# MCU48pin.net
KiCad netlist of a schematic drawn in Altium Designer
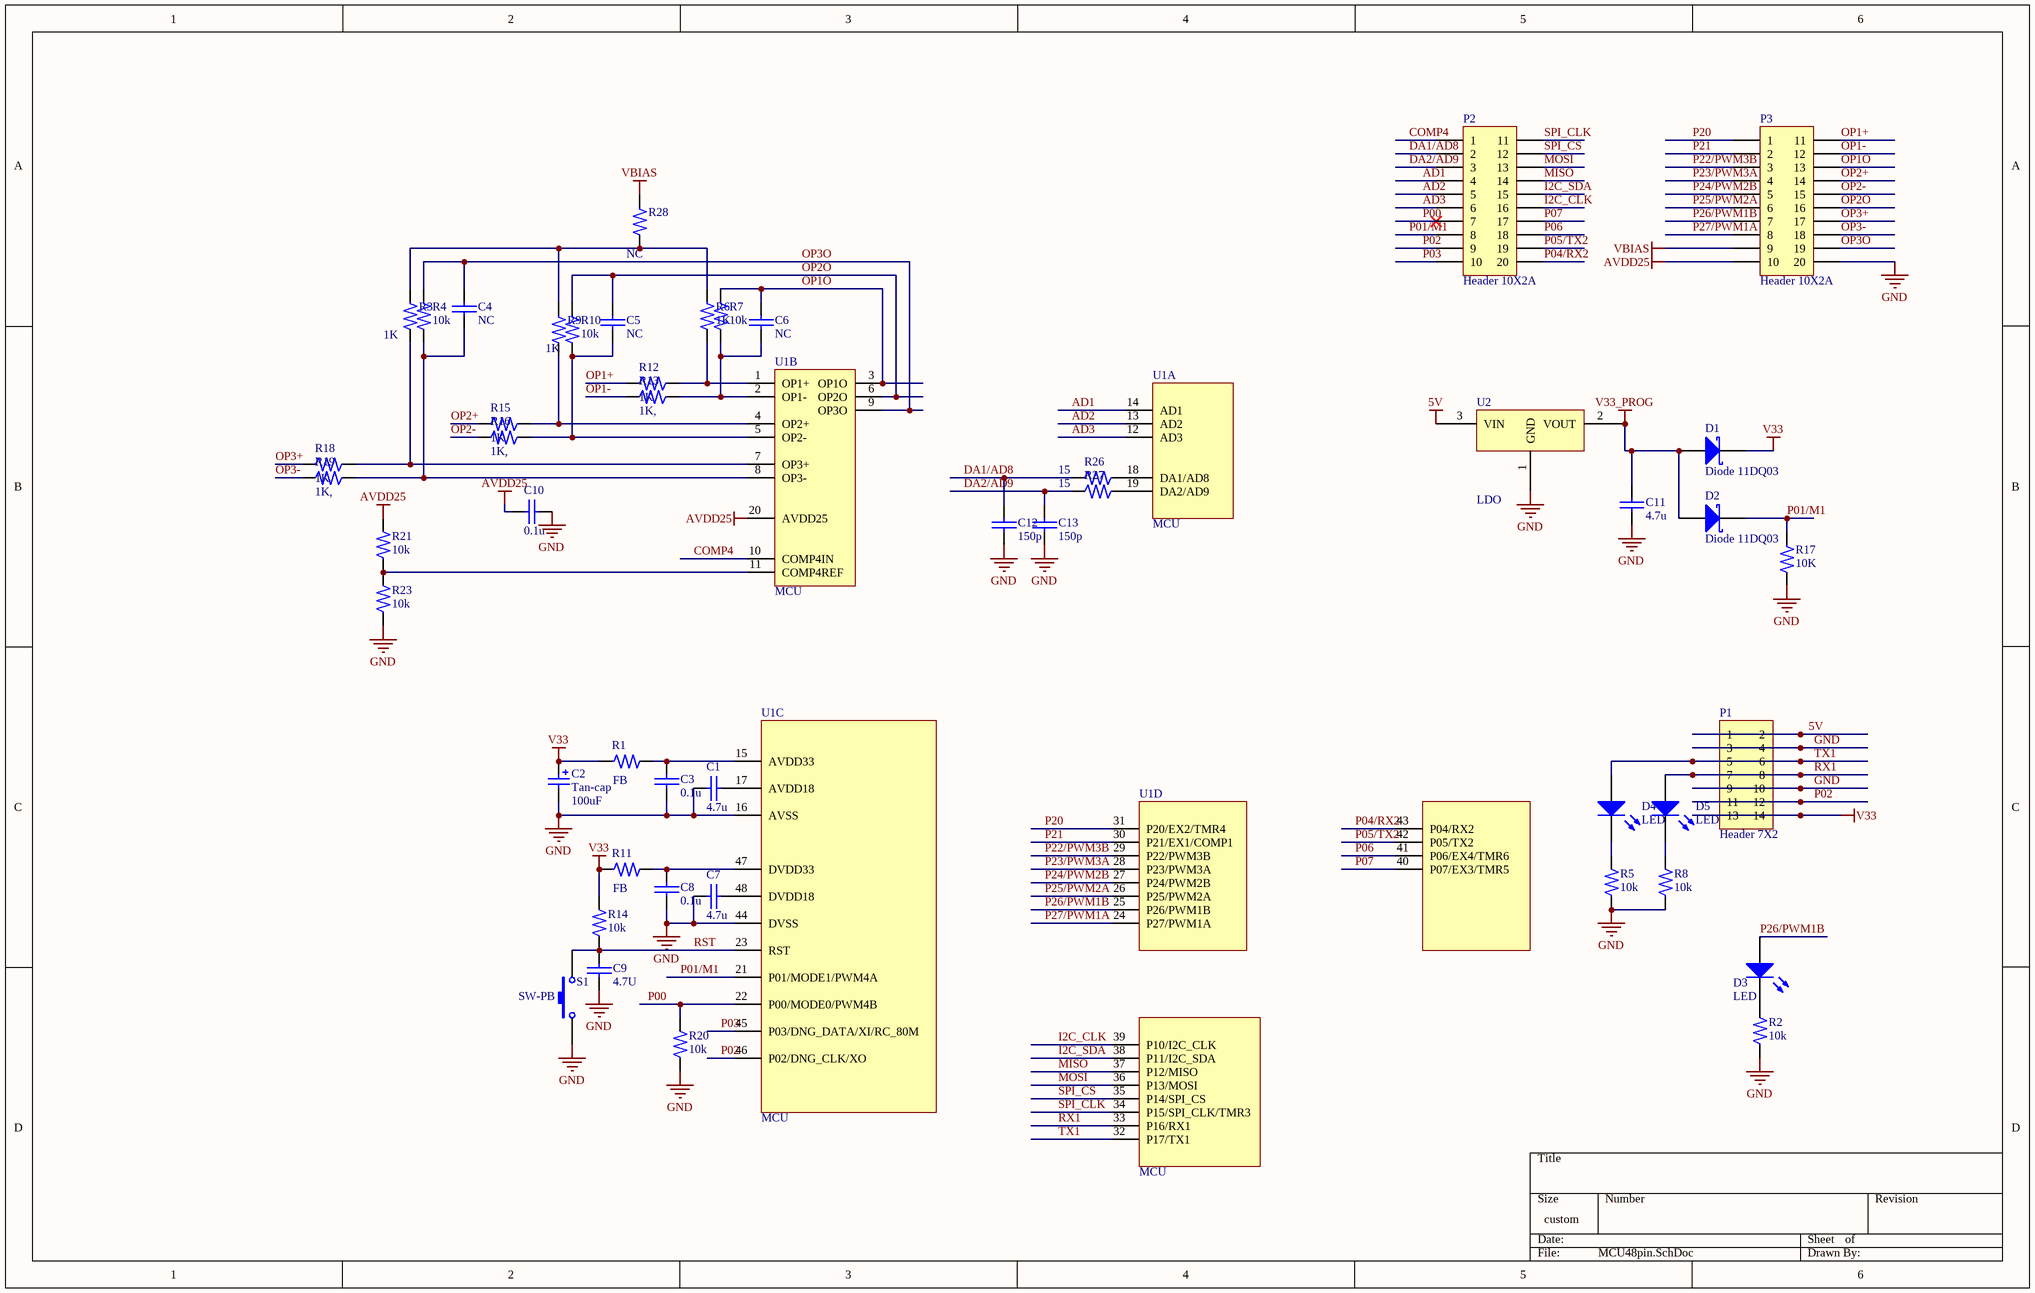
[diagram p0: MCU48pin.SchDoc]

(export (version "E")
  (design (tool "Eeschema 10.0.6"))
  (components
    (comp (ref "C1")
      (value "4.7u")
      (footprint "C0805")
      (description "CAP NL")
      (fields (field (name "MANUFACTURER") "Yageo") (field (name "PART NUMBER") "CC0603KRX7R9BB103"))
      (libsource (lib "black_V1") (part "CAP NP"))
    )
    (comp (ref "C2")
      (value "Tan-cap")
      (footprint "R1206w")
      (description "Polarized Capacitor (Radial)")
      (fields (field (name "ALTIUM_VALUE") "100uF") (field (name "PUBLISHER") "Altium Limited"))
      (libsource (lib "black_V1") (part "Cap Pol1"))
    )
    (comp (ref "C3")
      (value "0.1u")
      (footprint "1608[0603]")
      (description "CAP NL")
      (fields (field (name "MANUFACTURER") "Yageo") (field (name "PART NUMBER") "CC0603KRX7R9BB103"))
      (libsource (lib "black_V1") (part "CAP NP"))
    )
    (comp (ref "C4")
      (value "NC")
      (footprint "1608[0603]")
      (description "CAP NL")
      (fields (field (name "MANUFACTURER") "Yageo") (field (name "PART NUMBER") "CC0603KRX7R9BB103"))
      (libsource (lib "black_V1") (part "CAP NP"))
    )
    (comp (ref "C5")
      (value "NC")
      (footprint "1608[0603]")
      (description "CAP NL")
      (fields (field (name "MANUFACTURER") "Yageo") (field (name "PART NUMBER") "CC0603KRX7R9BB103"))
      (libsource (lib "black_V1") (part "CAP NP"))
    )
    (comp (ref "C6")
      (value "NC")
      (footprint "1608[0603]")
      (description "CAP NL")
      (fields (field (name "MANUFACTURER") "Yageo") (field (name "PART NUMBER") "CC0603KRX7R9BB103"))
      (libsource (lib "black_V1") (part "CAP NP"))
    )
    (comp (ref "C7")
      (value "4.7u")
      (footprint "C0805")
      (description "CAP NL")
      (fields (field (name "MANUFACTURER") "Yageo") (field (name "PART NUMBER") "CC0603KRX7R9BB103"))
      (libsource (lib "black_V1") (part "CAP NP"))
    )
    (comp (ref "C8")
      (value "0.1u")
      (footprint "1608[0603]")
      (description "CAP NL")
      (fields (field (name "MANUFACTURER") "Yageo") (field (name "PART NUMBER") "CC0603KRX7R9BB103"))
      (libsource (lib "black_V1") (part "CAP NP"))
    )
    (comp (ref "C9")
      (value "4.7U")
      (footprint "1608[0603]")
      (description "CAP NL")
      (fields (field (name "MANUFACTURER") "Yageo") (field (name "PART NUMBER") "CC0603KRX7R9BB103"))
      (libsource (lib "black_V1") (part "CAP NP"))
    )
    (comp (ref "C10")
      (value "0.1u")
      (footprint "1608[0603]")
      (description "CAP NL")
      (fields (field (name "MANUFACTURER") "Yageo") (field (name "PART NUMBER") "CC0603KRX7R9BB103"))
      (libsource (lib "black_V1") (part "CAP NP"))
    )
    (comp (ref "C11")
      (value "4.7u")
      (footprint "C0805")
      (description "CAP NL")
      (fields (field (name "MANUFACTURER") "Yageo") (field (name "PART NUMBER") "CC0603KRX7R9BB103"))
      (libsource (lib "black_V1") (part "CAP NP"))
    )
    (comp (ref "C12")
      (value "150p")
      (footprint "1608[0603]")
      (description "CAP NL")
      (fields (field (name "MANUFACTURER") "Yageo") (field (name "PART NUMBER") "CC0603KRX7R9BB103"))
      (libsource (lib "black_V1") (part "CAP NP"))
    )
    (comp (ref "C13")
      (value "150p")
      (footprint "1608[0603]")
      (description "CAP NL")
      (fields (field (name "MANUFACTURER") "Yageo") (field (name "PART NUMBER") "CC0603KRX7R9BB103"))
      (libsource (lib "black_V1") (part "CAP NP"))
    )
    (comp (ref "D1")
      (value "Diode 11DQ03")
      (footprint "D0603")
      (description "Schottky Rectifier")
      (fields (field (name "PUBLISHER") "Altium Limited"))
      (libsource (lib "Miscellaneous Devices") (part "Diode 11DQ03"))
    )
    (comp (ref "D2")
      (value "Diode 11DQ03")
      (footprint "D0603")
      (description "Schottky Rectifier")
      (fields (field (name "PUBLISHER") "Altium Limited"))
      (libsource (lib "Miscellaneous Devices") (part "Diode 11DQ03"))
    )
    (comp (ref "D3")
      (value "LED")
      (footprint "D0603")
      (description "Typical RED, GREEN, YELLOW, AMBER GaAs LED")
      (fields (field (name "PUBLISHER") "Altium Limited"))
      (libsource (lib "Miscellaneous Devices") (part "LED2"))
    )
    (comp (ref "D4")
      (value "LED")
      (footprint "D0603")
      (description "Typical RED, GREEN, YELLOW, AMBER GaAs LED")
      (fields (field (name "PUBLISHER") "Altium Limited"))
      (libsource (lib "Miscellaneous Devices") (part "LED2"))
    )
    (comp (ref "D5")
      (value "LED")
      (footprint "D0603")
      (description "Typical RED, GREEN, YELLOW, AMBER GaAs LED")
      (fields (field (name "PUBLISHER") "Altium Limited"))
      (libsource (lib "Miscellaneous Devices") (part "LED2"))
    )
    (comp (ref "P1")
      (value "Header 7X2")
      (footprint "HDR2X7")
      (description "Header, 7-Pin, Dual row")
      (fields (field (name "PUBLISHER") "Altium Limited"))
      (libsource (lib "Miscellaneous Connectors") (part "Header 7X2"))
    )
    (comp (ref "P2")
      (value "Header 10X2A")
      (footprint "HDR2X10_CEN")
      (description "Header, 10-Pin, Dual row")
      (fields (field (name "PUBLISHER") "Altium Limited"))
      (libsource (lib "Miscellaneous Connectors") (part "Header 10X2A"))
    )
    (comp (ref "P3")
      (value "Header 10X2A")
      (footprint "HDR2X10_CEN")
      (description "Header, 10-Pin, Dual row")
      (fields (field (name "PUBLISHER") "Altium Limited"))
      (libsource (lib "Miscellaneous Connectors") (part "Header 10X2A"))
    )
    (comp (ref "R1")
      (value "FB")
      (footprint "R0603")
      (description "RES")
      (fields (field (name "MANUFACTURER") "Yageo") (field (name "PART NUMBER") "RC0603JR-071KL"))
      (libsource (lib "black_V1") (part "RES"))
    )
    (comp (ref "R2")
      (value "10k")
      (footprint "R0603")
      (description "RES")
      (fields (field (name "MANUFACTURER") "Yageo") (field (name "PART NUMBER") "RC0603JR-071KL"))
      (libsource (lib "black_V1") (part "RES"))
    )
    (comp (ref "R3")
      (value "1K")
      (footprint "R0603")
      (description "RES")
      (fields (field (name "MANUFACTURER") "Yageo") (field (name "PART NUMBER") "RC0603JR-071KL"))
      (libsource (lib "black_V1") (part "RES"))
    )
    (comp (ref "R4")
      (value "10k")
      (footprint "R0603")
      (description "RES")
      (fields (field (name "MANUFACTURER") "Yageo") (field (name "PART NUMBER") "RC0603JR-071KL"))
      (libsource (lib "black_V1") (part "RES"))
    )
    (comp (ref "R5")
      (value "10k")
      (footprint "R0603")
      (description "RES")
      (fields (field (name "MANUFACTURER") "Yageo") (field (name "PART NUMBER") "RC0603JR-071KL"))
      (libsource (lib "black_V1") (part "RES"))
    )
    (comp (ref "R6")
      (value "1K")
      (footprint "R0603")
      (description "RES")
      (fields (field (name "MANUFACTURER") "Yageo") (field (name "PART NUMBER") "RC0603JR-071KL"))
      (libsource (lib "black_V1") (part "RES"))
    )
    (comp (ref "R7")
      (value "10k")
      (footprint "R0603")
      (description "RES")
      (fields (field (name "MANUFACTURER") "Yageo") (field (name "PART NUMBER") "RC0603JR-071KL"))
      (libsource (lib "black_V1") (part "RES"))
    )
    (comp (ref "R8")
      (value "10k")
      (footprint "R0603")
      (description "RES")
      (fields (field (name "MANUFACTURER") "Yageo") (field (name "PART NUMBER") "RC0603JR-071KL"))
      (libsource (lib "black_V1") (part "RES"))
    )
    (comp (ref "R9")
      (value "1K")
      (footprint "R0603")
      (description "RES")
      (fields (field (name "MANUFACTURER") "Yageo") (field (name "PART NUMBER") "RC0603JR-071KL"))
      (libsource (lib "black_V1") (part "RES"))
    )
    (comp (ref "R10")
      (value "10k")
      (footprint "R0603")
      (description "RES")
      (fields (field (name "MANUFACTURER") "Yageo") (field (name "PART NUMBER") "RC0603JR-071KL"))
      (libsource (lib "black_V1") (part "RES"))
    )
    (comp (ref "R11")
      (value "FB")
      (footprint "R0603")
      (description "RES")
      (fields (field (name "MANUFACTURER") "Yageo") (field (name "PART NUMBER") "RC0603JR-071KL"))
      (libsource (lib "black_V1") (part "RES"))
    )
    (comp (ref "R12")
      (value "1K")
      (footprint "R0603")
      (description "RES")
      (fields (field (name "MANUFACTURER") "Yageo") (field (name "PART NUMBER") "RC0603JR-071KL"))
      (libsource (lib "black_V1") (part "RES"))
    )
    (comp (ref "R13")
      (value "1K,")
      (footprint "R0603")
      (description "RES")
      (fields (field (name "MANUFACTURER") "Yageo") (field (name "PART NUMBER") "RC0603JR-071KL"))
      (libsource (lib "black_V1") (part "RES"))
    )
    (comp (ref "R14")
      (value "10k")
      (footprint "R0603")
      (description "RES")
      (fields (field (name "MANUFACTURER") "Yageo") (field (name "PART NUMBER") "RC0603JR-071KL"))
      (libsource (lib "black_V1") (part "RES"))
    )
    (comp (ref "R15")
      (value "1K")
      (footprint "R0603")
      (description "RES")
      (fields (field (name "MANUFACTURER") "Yageo") (field (name "PART NUMBER") "RC0603JR-071KL"))
      (libsource (lib "black_V1") (part "RES"))
    )
    (comp (ref "R16")
      (value "1K,")
      (footprint "R0603")
      (description "RES")
      (fields (field (name "MANUFACTURER") "Yageo") (field (name "PART NUMBER") "RC0603JR-071KL"))
      (libsource (lib "black_V1") (part "RES"))
    )
    (comp (ref "R17")
      (value "10K")
      (footprint "R0603")
      (description "RES")
      (fields (field (name "MANUFACTURER") "Yageo") (field (name "PART NUMBER") "RC0603JR-071KL"))
      (libsource (lib "black_V1") (part "RES"))
    )
    (comp (ref "R18")
      (value "1K")
      (footprint "R0603")
      (description "RES")
      (fields (field (name "MANUFACTURER") "Yageo") (field (name "PART NUMBER") "RC0603JR-071KL"))
      (libsource (lib "black_V1") (part "RES"))
    )
    (comp (ref "R19")
      (value "1K,")
      (footprint "R0603")
      (description "RES")
      (fields (field (name "MANUFACTURER") "Yageo") (field (name "PART NUMBER") "RC0603JR-071KL"))
      (libsource (lib "black_V1") (part "RES"))
    )
    (comp (ref "R20")
      (value "10k")
      (footprint "R0603")
      (description "RES")
      (fields (field (name "MANUFACTURER") "Yageo") (field (name "PART NUMBER") "RC0603JR-071KL"))
      (libsource (lib "black_V1") (part "RES"))
    )
    (comp (ref "R21")
      (value "10k")
      (footprint "R0603")
      (description "RES")
      (fields (field (name "MANUFACTURER") "Yageo") (field (name "PART NUMBER") "RC0603JR-071KL"))
      (libsource (lib "black_V1") (part "RES"))
    )
    (comp (ref "R23")
      (value "10k")
      (footprint "R0603")
      (description "RES")
      (fields (field (name "MANUFACTURER") "Yageo") (field (name "PART NUMBER") "RC0603JR-071KL"))
      (libsource (lib "black_V1") (part "RES"))
    )
    (comp (ref "R26")
      (value "15")
      (footprint "R0603")
      (description "RES")
      (fields (field (name "MANUFACTURER") "Yageo") (field (name "PART NUMBER") "RC0603JR-071KL"))
      (libsource (lib "black_V1") (part "RES"))
    )
    (comp (ref "R27")
      (value "15")
      (footprint "R0603")
      (description "RES")
      (fields (field (name "MANUFACTURER") "Yageo") (field (name "PART NUMBER") "RC0603JR-071KL"))
      (libsource (lib "black_V1") (part "RES"))
    )
    (comp (ref "R28")
      (value "NC")
      (footprint "R0603")
      (description "RES")
      (fields (field (name "MANUFACTURER") "Yageo") (field (name "PART NUMBER") "RC0603JR-071KL"))
      (libsource (lib "black_V1") (part "RES"))
    )
    (comp (ref "S1")
      (value "SW-PB")
      (footprint "SW")
      (description "Switch")
      (fields (field (name "PUBLISHER") "Altium Limited"))
      (libsource (lib "Miscellaneous Devices") (part "SW-PB"))
    )
    (comp (ref "U1") (value "MCU") (footprint "TSSOP48") (libsource (lib "mcu_evb") (part "MCU")))
    (comp (ref "U2") (value "LDO") (footprint "SOT223_M") (libsource (lib "mcu_evb") (part "LDO")))
  )
  (nets
    (net (code "1") (name "/AD1") (class "Default")
      (node (ref "P2") (pin "4") (pinfunction "4_4") (pintype "passive"))
      (node (ref "U1") (pin "14") (pinfunction "AD1_14") (pintype "passive"))
    )
    (net (code "2") (name "/AD2") (class "Default")
      (node (ref "P2") (pin "5") (pinfunction "5_5") (pintype "passive"))
      (node (ref "U1") (pin "13") (pinfunction "AD2_13") (pintype "passive"))
    )
    (net (code "3") (name "/AD3") (class "Default")
      (node (ref "P2") (pin "6") (pinfunction "6_6") (pintype "passive"))
      (node (ref "U1") (pin "12") (pinfunction "AD3_12") (pintype "passive"))
    )
    (net (code "4") (name "/COMP4") (class "Default")
      (node (ref "P2") (pin "1") (pinfunction "1_1") (pintype "passive"))
      (node (ref "U1") (pin "10") (pinfunction "COMP4IN_10") (pintype "passive"))
    )
    (net (code "5") (name "/DA1{slash}AD8") (class "Default")
      (node (ref "C12") (pin "1") (pinfunction "1_1") (pintype "passive"))
      (node (ref "P2") (pin "2") (pinfunction "2_2") (pintype "passive"))
      (node (ref "R26") (pin "2") (pintype "passive"))
    )
    (net (code "6") (name "/DA2{slash}AD9") (class "Default")
      (node (ref "C13") (pin "1") (pinfunction "1_1") (pintype "passive"))
      (node (ref "P2") (pin "3") (pinfunction "3_3") (pintype "passive"))
      (node (ref "R27") (pin "2") (pintype "passive"))
    )
    (net (code "7") (name "/I2C_CLK") (class "Default")
      (node (ref "P2") (pin "16") (pinfunction "16_16") (pintype "passive"))
      (node (ref "U1") (pin "39") (pinfunction "P10/I2C_CLK_39") (pintype "passive"))
    )
    (net (code "8") (name "/I2C_SDA") (class "Default")
      (node (ref "P2") (pin "15") (pinfunction "15_15") (pintype "passive"))
      (node (ref "U1") (pin "38") (pinfunction "P11/I2C_SDA_38") (pintype "passive"))
    )
    (net (code "9") (name "/MISO") (class "Default")
      (node (ref "P2") (pin "14") (pinfunction "14_14") (pintype "passive"))
      (node (ref "U1") (pin "37") (pinfunction "P12/MISO_37") (pintype "passive"))
    )
    (net (code "10") (name "/MOSI") (class "Default")
      (node (ref "P2") (pin "13") (pinfunction "13_13") (pintype "passive"))
      (node (ref "U1") (pin "36") (pinfunction "P13/MOSI_36") (pintype "passive"))
    )
    (net (code "11") (name "/OP1+") (class "Default")
      (node (ref "P3") (pin "11") (pinfunction "11_11") (pintype "passive"))
      (node (ref "R12") (pin "2") (pintype "passive"))
    )
    (net (code "12") (name "/OP1-") (class "Default")
      (node (ref "P3") (pin "12") (pinfunction "12_12") (pintype "passive"))
      (node (ref "R13") (pin "2") (pintype "passive"))
    )
    (net (code "13") (name "/OP1O") (class "Default")
      (node (ref "C6") (pin "1") (pinfunction "1_1") (pintype "passive"))
      (node (ref "P3") (pin "13") (pinfunction "13_13") (pintype "passive"))
      (node (ref "R7") (pin "1") (pintype "passive"))
      (node (ref "U1") (pin "3") (pinfunction "OP1O_3") (pintype "passive"))
    )
    (net (code "14") (name "/OP2+") (class "Default")
      (node (ref "P3") (pin "14") (pinfunction "14_14") (pintype "passive"))
      (node (ref "R15") (pin "2") (pintype "passive"))
    )
    (net (code "15") (name "/OP2-") (class "Default")
      (node (ref "P3") (pin "15") (pinfunction "15_15") (pintype "passive"))
      (node (ref "R16") (pin "2") (pintype "passive"))
    )
    (net (code "16") (name "/OP2O") (class "Default")
      (node (ref "C5") (pin "1") (pinfunction "1_1") (pintype "passive"))
      (node (ref "P3") (pin "16") (pinfunction "16_16") (pintype "passive"))
      (node (ref "R10") (pin "1") (pintype "passive"))
      (node (ref "U1") (pin "6") (pinfunction "OP2O_6") (pintype "passive"))
    )
    (net (code "17") (name "/OP3+") (class "Default")
      (node (ref "P3") (pin "17") (pinfunction "17_17") (pintype "passive"))
      (node (ref "R18") (pin "2") (pintype "passive"))
    )
    (net (code "18") (name "/OP3-") (class "Default")
      (node (ref "P3") (pin "18") (pinfunction "18_18") (pintype "passive"))
      (node (ref "R19") (pin "2") (pintype "passive"))
    )
    (net (code "19") (name "/OP3O") (class "Default")
      (node (ref "C4") (pin "1") (pinfunction "1_1") (pintype "passive"))
      (node (ref "P3") (pin "19") (pinfunction "19_19") (pintype "passive"))
      (node (ref "R4") (pin "1") (pintype "passive"))
      (node (ref "U1") (pin "9") (pinfunction "OP3O_9") (pintype "passive"))
    )
    (net (code "20") (name "/P00") (class "Default")
      (node (ref "P2") (pin "7") (pinfunction "7_7") (pintype "passive"))
      (node (ref "R20") (pin "2") (pintype "passive"))
      (node (ref "U1") (pin "22") (pinfunction "P00/MODE0/PWM4B_22") (pintype "passive"))
    )
    (net (code "21") (name "/P01{slash}M1") (class "Default")
      (node (ref "D2") (pin "2") (pinfunction "K_2") (pintype "passive"))
      (node (ref "P2") (pin "8") (pinfunction "8_8") (pintype "passive"))
      (node (ref "R17") (pin "1") (pintype "passive"))
      (node (ref "U1") (pin "21") (pinfunction "P01/MODE1/PWM4A_21") (pintype "passive"))
    )
    (net (code "22") (name "/P02") (class "Default")
      (node (ref "P1") (pin "11") (pinfunction "11_11") (pintype "passive"))
      (node (ref "P1") (pin "12") (pinfunction "12_12") (pintype "passive"))
      (node (ref "P2") (pin "9") (pinfunction "9_9") (pintype "passive"))
      (node (ref "U1") (pin "46") (pinfunction "P02/DNG_CLK/XO_46") (pintype "passive"))
    )
    (net (code "23") (name "/P03") (class "Default")
      (node (ref "P2") (pin "10") (pinfunction "10_10") (pintype "passive"))
      (node (ref "U1") (pin "45") (pinfunction "P03/DNG_DATA/XI/RC_80M_45") (pintype "passive"))
    )
    (net (code "24") (name "/P04{slash}RX2") (class "Default")
      (node (ref "P2") (pin "20") (pinfunction "20_20") (pintype "passive"))
      (node (ref "U1") (pin "43") (pinfunction "P04/RX2_43") (pintype "passive"))
    )
    (net (code "25") (name "/P05{slash}TX2") (class "Default")
      (node (ref "P2") (pin "19") (pinfunction "19_19") (pintype "passive"))
      (node (ref "U1") (pin "42") (pinfunction "P05/TX2_42") (pintype "passive"))
    )
    (net (code "26") (name "/P06") (class "Default")
      (node (ref "P2") (pin "18") (pinfunction "18_18") (pintype "passive"))
      (node (ref "U1") (pin "41") (pinfunction "P06/EX4/TMR6_41") (pintype "passive"))
    )
    (net (code "27") (name "/P07") (class "Default")
      (node (ref "P2") (pin "17") (pinfunction "17_17") (pintype "passive"))
      (node (ref "U1") (pin "40") (pinfunction "P07/EX3/TMR5_40") (pintype "passive"))
    )
    (net (code "28") (name "/P20") (class "Default")
      (node (ref "P3") (pin "1") (pinfunction "1_1") (pintype "passive"))
      (node (ref "U1") (pin "31") (pinfunction "P20/EX2/TMR4_31") (pintype "passive"))
    )
    (net (code "29") (name "/P21") (class "Default")
      (node (ref "P3") (pin "2") (pinfunction "2_2") (pintype "passive"))
      (node (ref "U1") (pin "30") (pinfunction "P21/EX1/COMP1_30") (pintype "passive"))
    )
    (net (code "30") (name "/P22{slash}PWM3B") (class "Default")
      (node (ref "P3") (pin "3") (pinfunction "3_3") (pintype "passive"))
      (node (ref "U1") (pin "29") (pinfunction "P22/PWM3B_29") (pintype "passive"))
    )
    (net (code "31") (name "/P23{slash}PWM3A") (class "Default")
      (node (ref "P3") (pin "4") (pinfunction "4_4") (pintype "passive"))
      (node (ref "U1") (pin "28") (pinfunction "P23/PWM3A_28") (pintype "passive"))
    )
    (net (code "32") (name "/P24{slash}PWM2B") (class "Default")
      (node (ref "P3") (pin "5") (pinfunction "5_5") (pintype "passive"))
      (node (ref "U1") (pin "27") (pinfunction "P24/PWM2B_27") (pintype "passive"))
    )
    (net (code "33") (name "/P25{slash}PWM2A") (class "Default")
      (node (ref "P3") (pin "6") (pinfunction "6_6") (pintype "passive"))
      (node (ref "U1") (pin "26") (pinfunction "P25/PWM2A_26") (pintype "passive"))
    )
    (net (code "34") (name "/P26{slash}PWM1B") (class "Default")
      (node (ref "D3") (pin "1") (pinfunction "A_1") (pintype "passive"))
      (node (ref "P3") (pin "7") (pinfunction "7_7") (pintype "passive"))
      (node (ref "U1") (pin "25") (pinfunction "P26/PWM1B_25") (pintype "passive"))
    )
    (net (code "35") (name "/P27{slash}PWM1A") (class "Default")
      (node (ref "P3") (pin "8") (pinfunction "8_8") (pintype "passive"))
      (node (ref "U1") (pin "24") (pinfunction "P27/PWM1A_24") (pintype "passive"))
    )
    (net (code "36") (name "/RST") (class "Default")
      (node (ref "C9") (pin "1") (pinfunction "1_1") (pintype "passive"))
      (node (ref "R14") (pin "1") (pintype "passive"))
      (node (ref "S1") (pin "2") (pinfunction "2_2") (pintype "passive"))
      (node (ref "U1") (pin "23") (pinfunction "RST_23") (pintype "passive"))
    )
    (net (code "37") (name "/RX1") (class "Default")
      (node (ref "D5") (pin "1") (pinfunction "A_1") (pintype "passive"))
      (node (ref "P1") (pin "7") (pinfunction "7_7") (pintype "passive"))
      (node (ref "P1") (pin "8") (pinfunction "8_8") (pintype "passive"))
      (node (ref "U1") (pin "33") (pinfunction "P16/RX1_33") (pintype "passive"))
    )
    (net (code "38") (name "/SPI_CLK") (class "Default")
      (node (ref "P2") (pin "11") (pinfunction "11_11") (pintype "passive"))
      (node (ref "U1") (pin "34") (pinfunction "P15/SPI_CLK/TMR3_34") (pintype "passive"))
    )
    (net (code "39") (name "/SPI_CS") (class "Default")
      (node (ref "P2") (pin "12") (pinfunction "12_12") (pintype "passive"))
      (node (ref "U1") (pin "35") (pinfunction "P14/SPI_CS_35") (pintype "passive"))
    )
    (net (code "40") (name "/TX1") (class "Default")
      (node (ref "D4") (pin "1") (pinfunction "A_1") (pintype "passive"))
      (node (ref "P1") (pin "5") (pinfunction "5_5") (pintype "passive"))
      (node (ref "P1") (pin "6") (pinfunction "6_6") (pintype "passive"))
      (node (ref "U1") (pin "32") (pinfunction "P17/TX1_32") (pintype "passive"))
    )
    (net (code "41") (name "5V") (class "Default")
      (node (ref "P1") (pin "1") (pinfunction "1_1") (pintype "passive"))
      (node (ref "P1") (pin "2") (pinfunction "2_2") (pintype "passive"))
      (node (ref "U2") (pin "3") (pinfunction "VIN_3") (pintype "passive"))
    )
    (net (code "42") (name "AVDD25") (class "Default")
      (node (ref "C10") (pin "1") (pinfunction "1_1") (pintype "passive"))
      (node (ref "P3") (pin "10") (pinfunction "10_10") (pintype "passive"))
      (node (ref "R21") (pin "2") (pintype "passive"))
      (node (ref "U1") (pin "20") (pinfunction "AVDD25_20") (pintype "passive"))
    )
    (net (code "43") (name "GND") (class "Default")
      (node (ref "C1") (pin "1") (pinfunction "1_1") (pintype "passive"))
      (node (ref "C10") (pin "2") (pinfunction "2_2") (pintype "passive"))
      (node (ref "C11") (pin "1") (pinfunction "1_1") (pintype "passive"))
      (node (ref "C12") (pin "2") (pinfunction "2_2") (pintype "passive"))
      (node (ref "C13") (pin "2") (pinfunction "2_2") (pintype "passive"))
      (node (ref "C2") (pin "2") (pinfunction "2_2") (pintype "passive"))
      (node (ref "C3") (pin "2") (pinfunction "2_2") (pintype "passive"))
      (node (ref "C7") (pin "1") (pinfunction "1_1") (pintype "passive"))
      (node (ref "C8") (pin "2") (pinfunction "2_2") (pintype "passive"))
      (node (ref "C9") (pin "2") (pinfunction "2_2") (pintype "passive"))
      (node (ref "P1") (pin "10") (pinfunction "10_10") (pintype "passive"))
      (node (ref "P1") (pin "3") (pinfunction "3_3") (pintype "passive"))
      (node (ref "P1") (pin "4") (pinfunction "4_4") (pintype "passive"))
      (node (ref "P1") (pin "9") (pinfunction "9_9") (pintype "passive"))
      (node (ref "P3") (pin "20") (pinfunction "20_20") (pintype "passive"))
      (node (ref "R17") (pin "2") (pintype "passive"))
      (node (ref "R2") (pin "1") (pintype "passive"))
      (node (ref "R20") (pin "1") (pintype "passive"))
      (node (ref "R23") (pin "1") (pintype "passive"))
      (node (ref "R5") (pin "1") (pintype "passive"))
      (node (ref "R8") (pin "1") (pintype "passive"))
      (node (ref "S1") (pin "1") (pinfunction "1_1") (pintype "passive"))
      (node (ref "U1") (pin "16") (pinfunction "AVSS_16") (pintype "passive"))
      (node (ref "U1") (pin "44") (pinfunction "DVSS_44") (pintype "passive"))
      (node (ref "U2") (pin "1") (pinfunction "GND_1") (pintype "passive"))
    )
    (net (code "44") (name "Net-(D3-K)") (class "Default")
      (node (ref "D3") (pin "2") (pinfunction "K_2") (pintype "passive"))
      (node (ref "R2") (pin "2") (pintype "passive"))
    )
    (net (code "45") (name "Net-(D4-K)") (class "Default")
      (node (ref "D4") (pin "2") (pinfunction "K_2") (pintype "passive"))
      (node (ref "R5") (pin "2") (pintype "passive"))
    )
    (net (code "46") (name "Net-(D5-K)") (class "Default")
      (node (ref "D5") (pin "2") (pinfunction "K_2") (pintype "passive"))
      (node (ref "R8") (pin "2") (pintype "passive"))
    )
    (net (code "47") (name "Net-(R28-Pad2)") (class "Default")
      (node (ref "R28") (pin "2") (pintype "passive"))
      (node (ref "R3") (pin "1") (pintype "passive"))
      (node (ref "R6") (pin "1") (pintype "passive"))
      (node (ref "R9") (pin "1") (pintype "passive"))
    )
    (net (code "48") (name "Net-(U1A-DA1{slash}AD8)") (class "Default")
      (node (ref "R26") (pin "1") (pintype "passive"))
      (node (ref "U1") (pin "18") (pinfunction "DA1/AD8_18") (pintype "passive"))
    )
    (net (code "49") (name "Net-(U1A-DA2{slash}AD9)") (class "Default")
      (node (ref "R27") (pin "1") (pintype "passive"))
      (node (ref "U1") (pin "19") (pinfunction "DA2/AD9_19") (pintype "passive"))
    )
    (net (code "50") (name "Net-(U1B-COMP4REF)") (class "Default")
      (node (ref "R21") (pin "1") (pintype "passive"))
      (node (ref "R23") (pin "2") (pintype "passive"))
      (node (ref "U1") (pin "11") (pinfunction "COMP4REF_11") (pintype "passive"))
    )
    (net (code "51") (name "Net-(U1B-OP1+)") (class "Default")
      (node (ref "R12") (pin "1") (pintype "passive"))
      (node (ref "R6") (pin "2") (pintype "passive"))
      (node (ref "U1") (pin "1") (pinfunction "OP1+_1") (pintype "passive"))
    )
    (net (code "52") (name "Net-(U1B-OP1-)") (class "Default")
      (node (ref "C6") (pin "2") (pinfunction "2_2") (pintype "passive"))
      (node (ref "R13") (pin "1") (pintype "passive"))
      (node (ref "R7") (pin "2") (pintype "passive"))
      (node (ref "U1") (pin "2") (pinfunction "OP1-_2") (pintype "passive"))
    )
    (net (code "53") (name "Net-(U1B-OP2+)") (class "Default")
      (node (ref "R15") (pin "1") (pintype "passive"))
      (node (ref "R9") (pin "2") (pintype "passive"))
      (node (ref "U1") (pin "4") (pinfunction "OP2+_4") (pintype "passive"))
    )
    (net (code "54") (name "Net-(U1B-OP2-)") (class "Default")
      (node (ref "C5") (pin "2") (pinfunction "2_2") (pintype "passive"))
      (node (ref "R10") (pin "2") (pintype "passive"))
      (node (ref "R16") (pin "1") (pintype "passive"))
      (node (ref "U1") (pin "5") (pinfunction "OP2-_5") (pintype "passive"))
    )
    (net (code "55") (name "Net-(U1B-OP3+)") (class "Default")
      (node (ref "R18") (pin "1") (pintype "passive"))
      (node (ref "R3") (pin "2") (pintype "passive"))
      (node (ref "U1") (pin "7") (pinfunction "OP3+_7") (pintype "passive"))
    )
    (net (code "56") (name "Net-(U1B-OP3-)") (class "Default")
      (node (ref "C4") (pin "2") (pinfunction "2_2") (pintype "passive"))
      (node (ref "R19") (pin "1") (pintype "passive"))
      (node (ref "R4") (pin "2") (pintype "passive"))
      (node (ref "U1") (pin "8") (pinfunction "OP3-_8") (pintype "passive"))
    )
    (net (code "57") (name "Net-(U1C-AVDD18)") (class "Default")
      (node (ref "C1") (pin "2") (pinfunction "2_2") (pintype "passive"))
      (node (ref "U1") (pin "17") (pinfunction "AVDD18_17") (pintype "passive"))
    )
    (net (code "58") (name "Net-(U1C-AVDD33)") (class "Default")
      (node (ref "C3") (pin "1") (pinfunction "1_1") (pintype "passive"))
      (node (ref "R1") (pin "2") (pintype "passive"))
      (node (ref "U1") (pin "15") (pinfunction "AVDD33_15") (pintype "passive"))
    )
    (net (code "59") (name "Net-(U1C-DVDD18)") (class "Default")
      (node (ref "C7") (pin "2") (pinfunction "2_2") (pintype "passive"))
      (node (ref "U1") (pin "48") (pinfunction "DVDD18_48") (pintype "passive"))
    )
    (net (code "60") (name "Net-(U1C-DVDD33)") (class "Default")
      (node (ref "C8") (pin "1") (pinfunction "1_1") (pintype "passive"))
      (node (ref "R11") (pin "2") (pintype "passive"))
      (node (ref "U1") (pin "47") (pinfunction "DVDD33_47") (pintype "passive"))
    )
    (net (code "61") (name "V33") (class "Default")
      (node (ref "C2") (pin "1") (pinfunction "1_1") (pintype "passive"))
      (node (ref "D1") (pin "2") (pinfunction "K_2") (pintype "passive"))
      (node (ref "P1") (pin "13") (pinfunction "13_13") (pintype "passive"))
      (node (ref "P1") (pin "14") (pinfunction "14_14") (pintype "passive"))
      (node (ref "R1") (pin "1") (pintype "passive"))
      (node (ref "R11") (pin "1") (pintype "passive"))
      (node (ref "R14") (pin "2") (pintype "passive"))
    )
    (net (code "62") (name "V33_PROG") (class "Default")
      (node (ref "C11") (pin "2") (pinfunction "2_2") (pintype "passive"))
      (node (ref "D1") (pin "1") (pinfunction "A_1") (pintype "passive"))
      (node (ref "D2") (pin "1") (pinfunction "A_1") (pintype "passive"))
      (node (ref "U2") (pin "2") (pinfunction "VOUT_2") (pintype "passive"))
    )
    (net (code "63") (name "VBIAS") (class "Default")
      (node (ref "P3") (pin "9") (pinfunction "9_9") (pintype "passive"))
      (node (ref "R28") (pin "1") (pintype "passive"))
    )
  )
)
